# line5_2_2.net
KiCad netlist of a schematic drawn in EAGLE
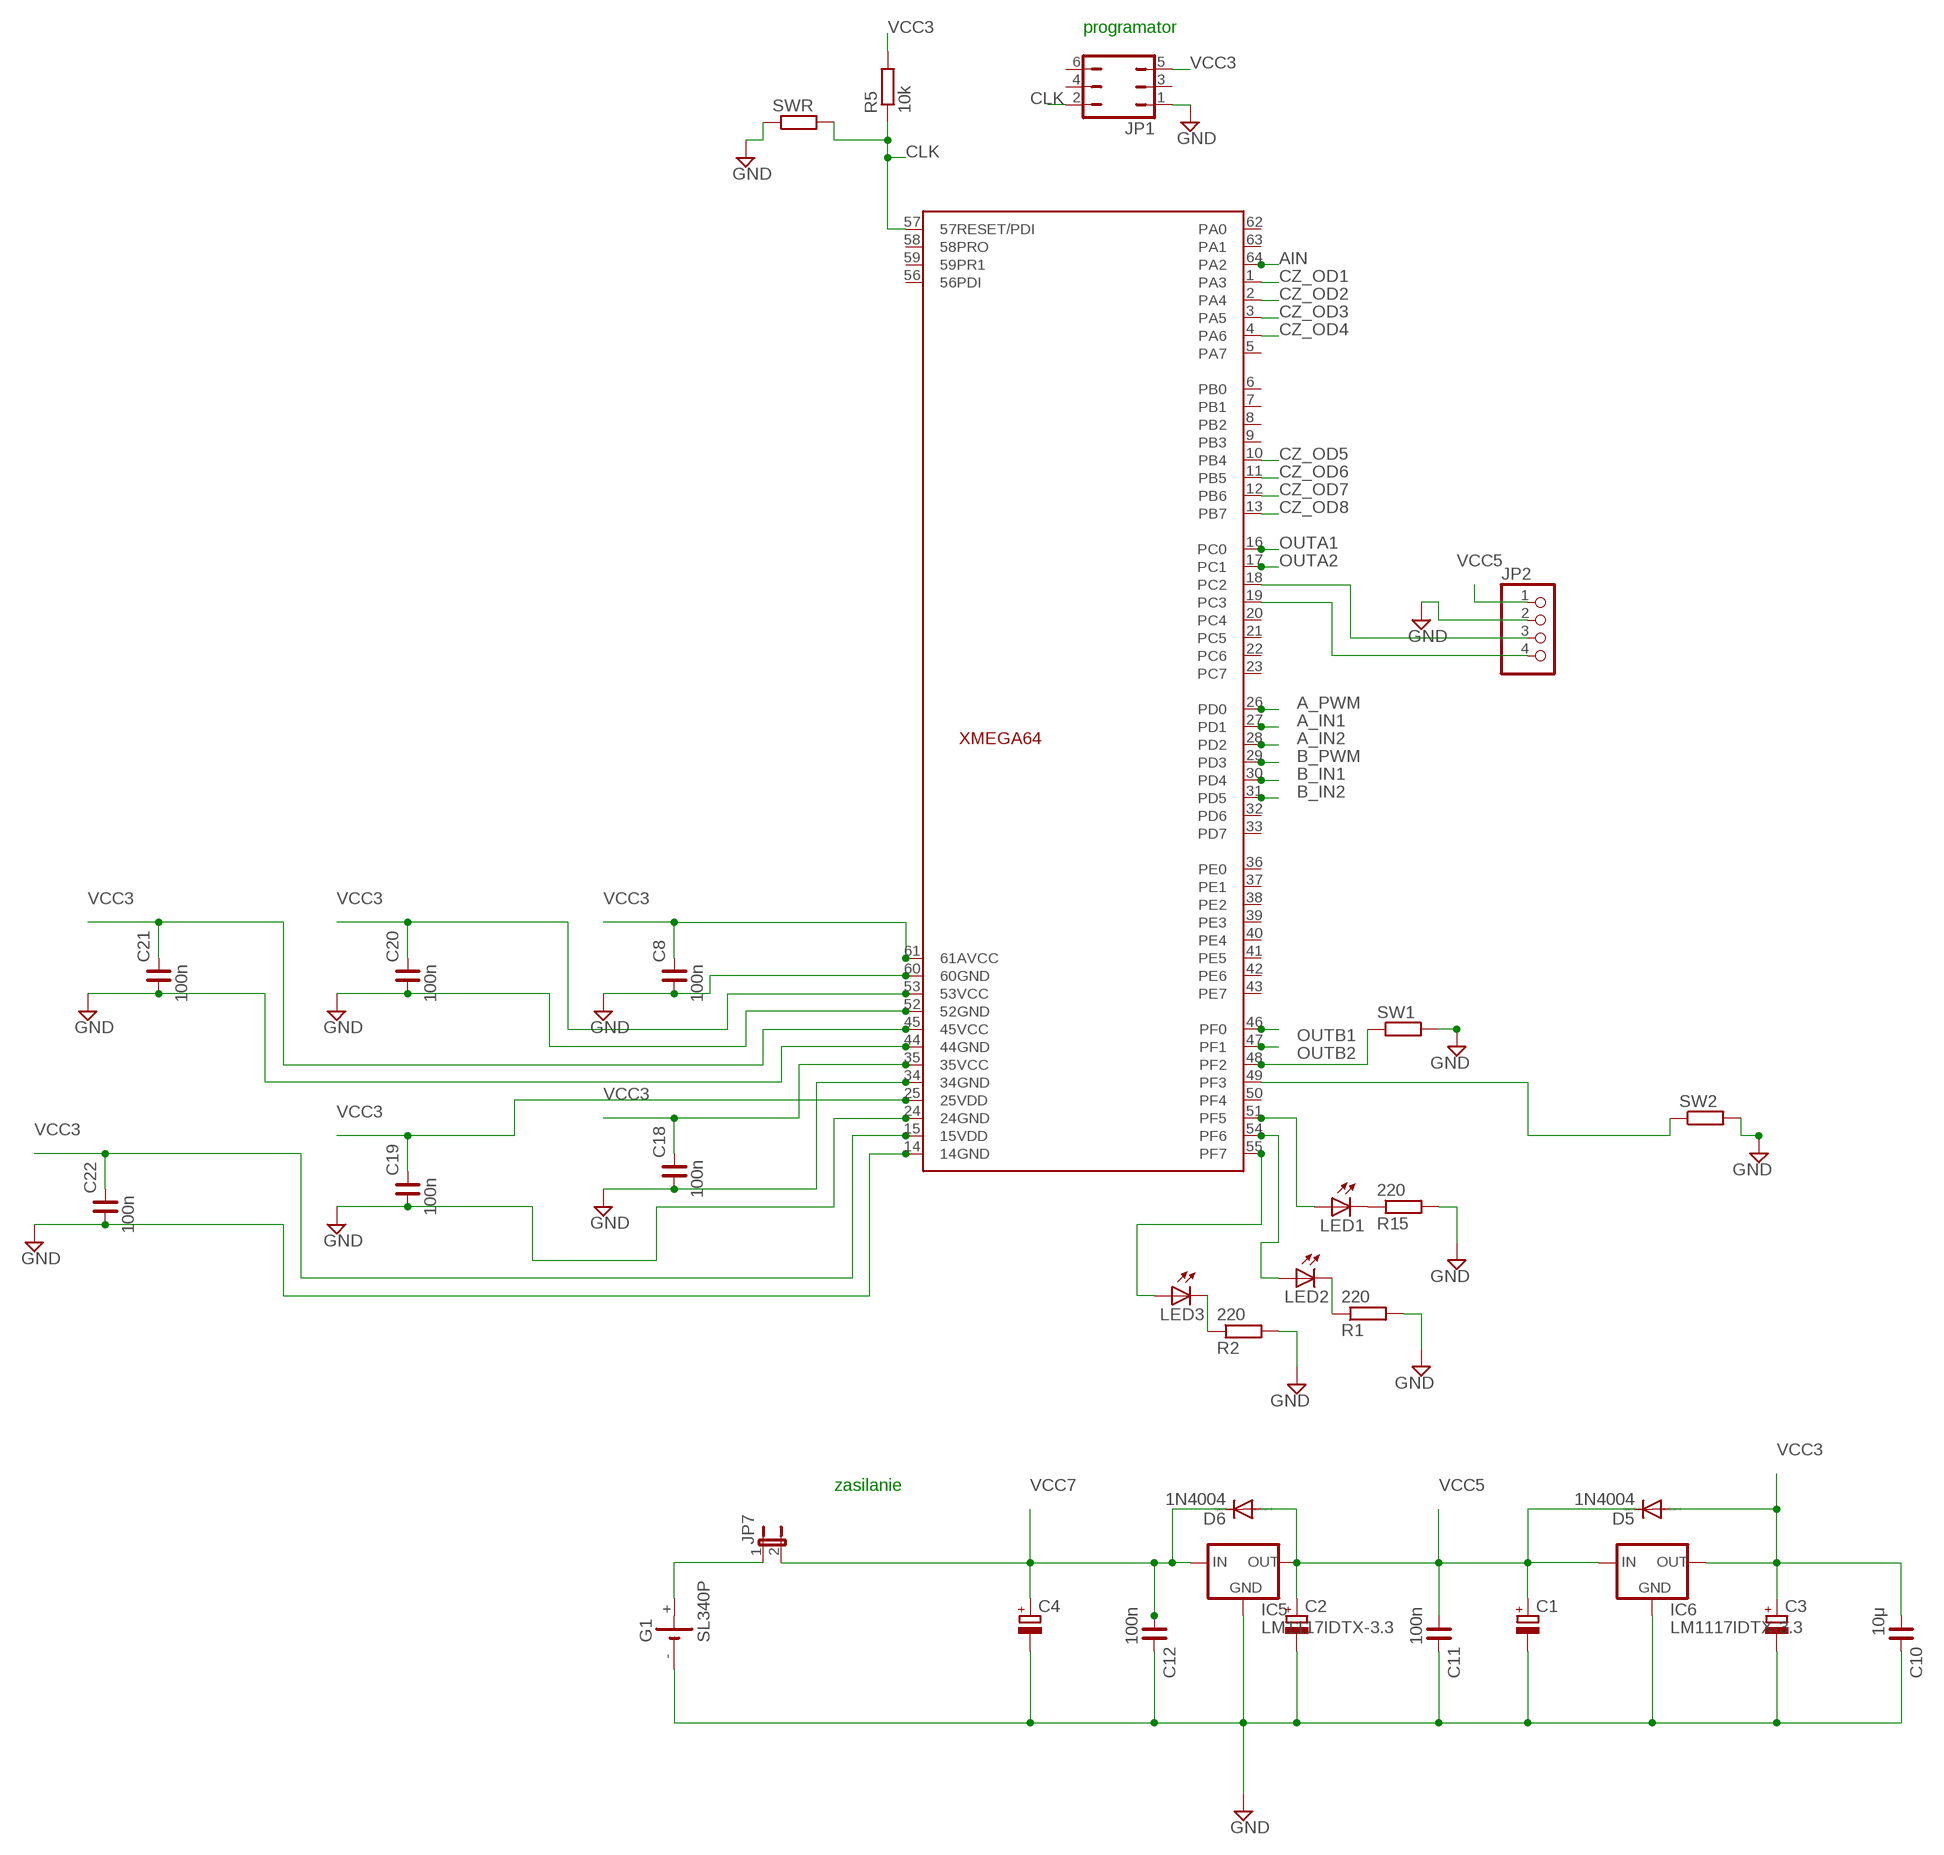
[diagram p0: schematic, sheet 1, part 1 of 2]
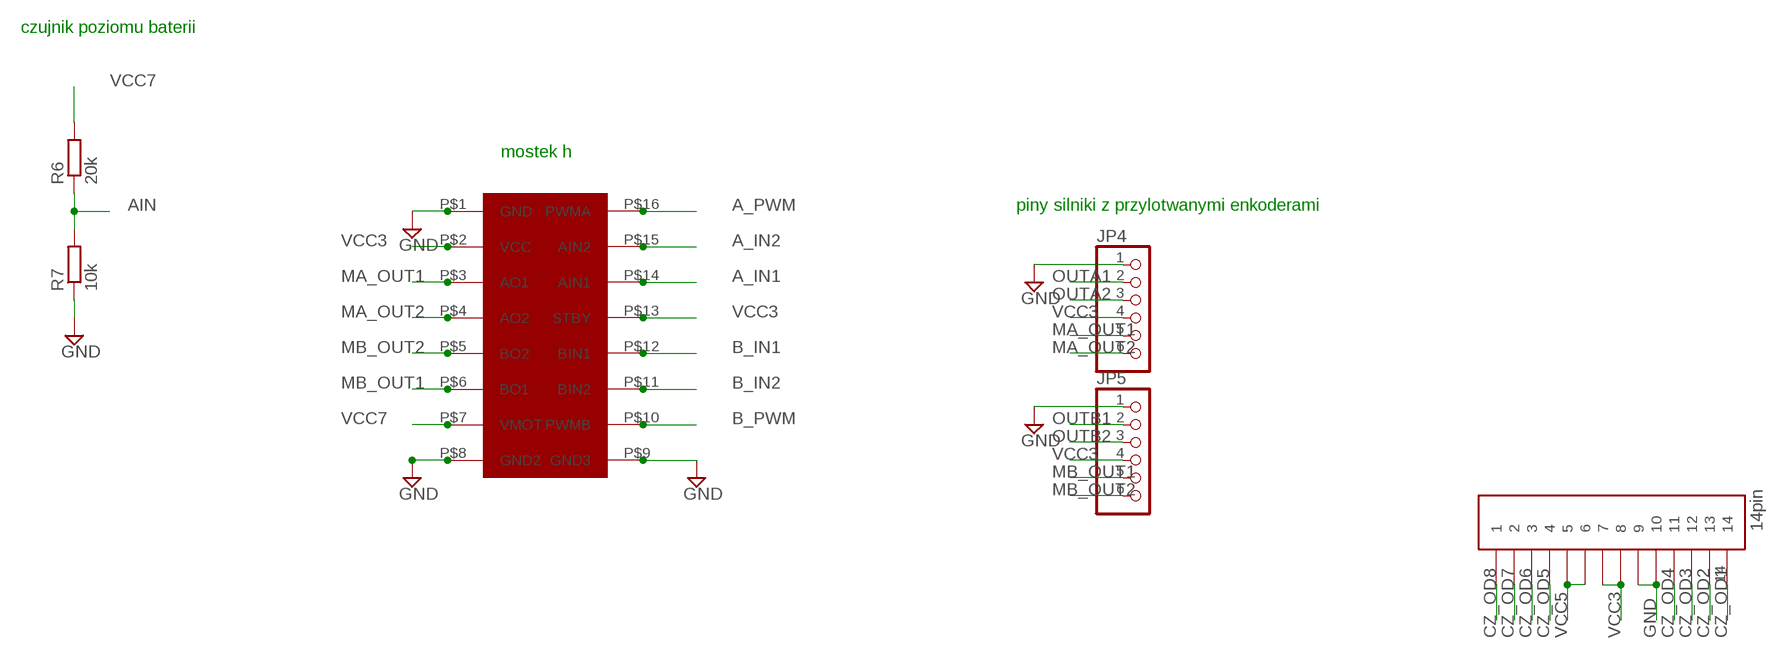
[diagram p1: schematic, sheet 1, part 2 of 2]

(export (version "E")
  (design (tool "Eeschema 10.0.6"))
  (components
    (comp (ref "C1")
      (value "CPOL-EU153CLV-0810")
      (footprint "eagle-import:153CLV-0810")
      (libsource (lib "eagle-import") (part "CPOL-EU153CLV-0810"))
    )
    (comp (ref "C2")
      (value "CPOL-EU153CLV-0810")
      (footprint "eagle-import:153CLV-0810")
      (libsource (lib "eagle-import") (part "CPOL-EU153CLV-0810"))
    )
    (comp (ref "C3")
      (value "CPOL-EU153CLV-0810")
      (footprint "eagle-import:153CLV-0810")
      (libsource (lib "eagle-import") (part "CPOL-EU153CLV-0810"))
    )
    (comp (ref "C4")
      (value "CPOL-EU153CLV-0810")
      (footprint "eagle-import:153CLV-0810")
      (libsource (lib "eagle-import") (part "CPOL-EU153CLV-0810"))
    )
    (comp (ref "C8")
      (value "100n")
      (footprint "eagle-import:C1206")
      (libsource (lib "eagle-import") (part "C_1206"))
    )
    (comp (ref "C10")
      (value "10μ")
      (footprint "eagle-import:C1206")
      (libsource (lib "eagle-import") (part "C_1206"))
    )
    (comp (ref "C11")
      (value "100n")
      (footprint "eagle-import:C1206")
      (libsource (lib "eagle-import") (part "C_1206"))
    )
    (comp (ref "C12")
      (value "100n")
      (footprint "eagle-import:C1206")
      (libsource (lib "eagle-import") (part "C_1206"))
    )
    (comp (ref "C18")
      (value "100n")
      (footprint "eagle-import:C1206")
      (libsource (lib "eagle-import") (part "C_1206"))
    )
    (comp (ref "C19")
      (value "100n")
      (footprint "eagle-import:C1206")
      (libsource (lib "eagle-import") (part "C_1206"))
    )
    (comp (ref "C20")
      (value "100n")
      (footprint "eagle-import:C1206")
      (libsource (lib "eagle-import") (part "C_1206"))
    )
    (comp (ref "C21")
      (value "100n")
      (footprint "eagle-import:C1206")
      (libsource (lib "eagle-import") (part "C_1206"))
    )
    (comp (ref "C22")
      (value "100n")
      (footprint "eagle-import:C1206")
      (libsource (lib "eagle-import") (part "C_1206"))
    )
    (comp (ref "D5")
      (value "1N4004")
      (footprint "eagle-import:DO41-10")
      (libsource (lib "eagle-import") (part "1N4004"))
    )
    (comp (ref "D6")
      (value "1N4004")
      (footprint "eagle-import:DO41-10")
      (libsource (lib "eagle-import") (part "1N4004"))
    )
    (comp (ref "G1")
      (value "SL340P")
      (footprint "eagle-import:SL-340_P3.6V")
      (libsource (lib "eagle-import") (part "SL340P"))
    )
    (comp (ref "IC5")
      (value "LM1117IDTX-3.3")
      (footprint "eagle-import:TO252")
      (libsource (lib "eagle-import") (part "LM1117IDTX-3.3"))
    )
    (comp (ref "IC6")
      (value "LM1117IDTX-3.3")
      (footprint "eagle-import:TO252")
      (libsource (lib "eagle-import") (part "LM1117IDTX-3.3"))
    )
    (comp (ref "JP1")
      (value "JP3Q")
      (footprint "eagle-import:JP3Q")
      (libsource (lib "eagle-import") (part "JP3Q"))
    )
    (comp (ref "JP2")
      (value "PINHD-1X4")
      (footprint "eagle-import:1X04")
      (libsource (lib "eagle-import") (part "PINHD-1X4"))
    )
    (comp (ref "JP4")
      (value "PINHD-1X6")
      (footprint "eagle-import:1X06")
      (libsource (lib "eagle-import") (part "PINHD-1X6"))
    )
    (comp (ref "JP5")
      (value "PINHD-1X6")
      (footprint "eagle-import:1X06")
      (libsource (lib "eagle-import") (part "PINHD-1X6"))
    )
    (comp (ref "JP7")
      (value "JP1E")
      (footprint "eagle-import:JP1")
      (libsource (lib "eagle-import") (part "JP1E"))
    )
    (comp (ref "LED1")
      (value "LEDSMT1206")
      (footprint "eagle-import:1206")
      (libsource (lib "eagle-import") (part "LEDSMT1206"))
    )
    (comp (ref "LED2")
      (value "LEDSMT1206")
      (footprint "eagle-import:1206")
      (libsource (lib "eagle-import") (part "LEDSMT1206"))
    )
    (comp (ref "LED3")
      (value "LEDSMT1206")
      (footprint "eagle-import:1206")
      (libsource (lib "eagle-import") (part "LEDSMT1206"))
    )
    (comp (ref "R1")
      (value "220")
      (footprint "eagle-import:R0805")
      (libsource (lib "eagle-import") (part "R-EU_R0805"))
    )
    (comp (ref "R2")
      (value "220")
      (footprint "eagle-import:R0805")
      (libsource (lib "eagle-import") (part "R-EU_R0805"))
    )
    (comp (ref "R5")
      (value "10k")
      (footprint "eagle-import:R0805")
      (libsource (lib "eagle-import") (part "R-EU_R0805"))
    )
    (comp (ref "R6")
      (value "20k")
      (footprint "eagle-import:R0805")
      (libsource (lib "eagle-import") (part "R-EU_R0805"))
    )
    (comp (ref "R7")
      (value "10k")
      (footprint "eagle-import:R0805")
      (libsource (lib "eagle-import") (part "R-EU_R0805"))
    )
    (comp (ref "R15")
      (value "220")
      (footprint "eagle-import:R0805")
      (libsource (lib "eagle-import") (part "R-EU_R0805"))
    )
    (comp (ref "SW1")
      (value "R-EU_R1206")
      (footprint "eagle-import:R1206")
      (libsource (lib "eagle-import") (part "R-EU_R1206"))
    )
    (comp (ref "SW2")
      (value "R-EU_R1206")
      (footprint "eagle-import:R1206")
      (libsource (lib "eagle-import") (part "R-EU_R1206"))
    )
    (comp (ref "SWR")
      (value "R-EU_R1206")
      (footprint "eagle-import:R1206")
      (libsource (lib "eagle-import") (part "R-EU_R1206"))
    )
    (comp (ref "U$1")
      (value "POLULU713")
      (footprint "eagle-import:POLULU713")
      (libsource (lib "eagle-import") (part "POLULU713"))
    )
    (comp (ref "U$2")
      (value "14PIN")
      (footprint "eagle-import:14PIN")
      (libsource (lib "eagle-import") (part "14PIN"))
    )
    (comp (ref "XMEGA64")
      (value "XMEGA64C3TQFP64")
      (footprint "eagle-import:TQFP64")
      (libsource (lib "eagle-import") (part "XMEGA64C3TQFP64"))
    )
  )
  (nets
    (net (code "1") (name "/AIN") (class "Default")
      (node (ref "R6") (pin "1") (pinfunction "1_1") (pintype "passive"))
      (node (ref "R7") (pin "2") (pinfunction "2_2") (pintype "passive"))
      (node (ref "XMEGA64") (pin "64") (pinfunction "PA2_64") (pintype "bidirectional"))
    )
    (net (code "2") (name "/A_IN1") (class "Default")
      (node (ref "U$1") (pin "P$14") (pinfunction "AIN1_P$14") (pintype "bidirectional"))
      (node (ref "XMEGA64") (pin "27") (pinfunction "PD1_27") (pintype "bidirectional"))
    )
    (net (code "3") (name "/A_IN2") (class "Default")
      (node (ref "U$1") (pin "P$15") (pinfunction "AIN2_P$15") (pintype "bidirectional"))
      (node (ref "XMEGA64") (pin "28") (pinfunction "PD2_28") (pintype "bidirectional"))
    )
    (net (code "4") (name "/A_PWM") (class "Default")
      (node (ref "U$1") (pin "P$16") (pinfunction "PWMA_P$16") (pintype "bidirectional"))
      (node (ref "XMEGA64") (pin "26") (pinfunction "PD0_26") (pintype "bidirectional"))
    )
    (net (code "5") (name "/B_IN1") (class "Default")
      (node (ref "U$1") (pin "P$12") (pinfunction "BIN1_P$12") (pintype "bidirectional"))
      (node (ref "XMEGA64") (pin "30") (pinfunction "PD4_30") (pintype "bidirectional"))
    )
    (net (code "6") (name "/B_IN2") (class "Default")
      (node (ref "U$1") (pin "P$11") (pinfunction "BIN2_P$11") (pintype "bidirectional"))
      (node (ref "XMEGA64") (pin "31") (pinfunction "PD5_31") (pintype "bidirectional"))
    )
    (net (code "7") (name "/B_PWM") (class "Default")
      (node (ref "U$1") (pin "P$10") (pinfunction "PWMB_P$10") (pintype "bidirectional"))
      (node (ref "XMEGA64") (pin "29") (pinfunction "PD3_29") (pintype "bidirectional"))
    )
    (net (code "8") (name "/CLK") (class "Default")
      (node (ref "JP1") (pin "2") (pinfunction "2_2") (pintype "passive"))
      (node (ref "R5") (pin "1") (pinfunction "1_1") (pintype "passive"))
      (node (ref "SWR") (pin "2") (pinfunction "2_2") (pintype "passive"))
      (node (ref "XMEGA64") (pin "57") (pinfunction "57RESET/PDI_57") (pintype "bidirectional"))
    )
    (net (code "9") (name "/CZ_OD1") (class "Default")
      (node (ref "U$2") (pin "14") (pinfunction "14_14") (pintype "bidirectional"))
      (node (ref "XMEGA64") (pin "1") (pinfunction "PA3_1") (pintype "bidirectional"))
    )
    (net (code "10") (name "/CZ_OD2") (class "Default")
      (node (ref "U$2") (pin "13") (pinfunction "13_13") (pintype "bidirectional"))
      (node (ref "XMEGA64") (pin "2") (pinfunction "PA4_2") (pintype "bidirectional"))
    )
    (net (code "11") (name "/CZ_OD3") (class "Default")
      (node (ref "U$2") (pin "12") (pinfunction "12_12") (pintype "bidirectional"))
      (node (ref "XMEGA64") (pin "3") (pinfunction "PA5_3") (pintype "bidirectional"))
    )
    (net (code "12") (name "/CZ_OD4") (class "Default")
      (node (ref "U$2") (pin "11") (pinfunction "11_11") (pintype "bidirectional"))
      (node (ref "XMEGA64") (pin "4") (pinfunction "PA6_4") (pintype "bidirectional"))
    )
    (net (code "13") (name "/CZ_OD5") (class "Default")
      (node (ref "U$2") (pin "4") (pinfunction "4_4") (pintype "bidirectional"))
      (node (ref "XMEGA64") (pin "10") (pinfunction "PB4_10") (pintype "bidirectional"))
    )
    (net (code "14") (name "/CZ_OD6") (class "Default")
      (node (ref "U$2") (pin "3") (pinfunction "3_3") (pintype "bidirectional"))
      (node (ref "XMEGA64") (pin "11") (pinfunction "PB5_11") (pintype "bidirectional"))
    )
    (net (code "15") (name "/CZ_OD7") (class "Default")
      (node (ref "U$2") (pin "2") (pinfunction "2_2") (pintype "bidirectional"))
      (node (ref "XMEGA64") (pin "12") (pinfunction "PB6_12") (pintype "bidirectional"))
    )
    (net (code "16") (name "/CZ_OD8") (class "Default")
      (node (ref "U$2") (pin "1") (pinfunction "1_1") (pintype "bidirectional"))
      (node (ref "XMEGA64") (pin "13") (pinfunction "PB7_13") (pintype "bidirectional"))
    )
    (net (code "17") (name "/MA_OUT1") (class "Default")
      (node (ref "JP4") (pin "5") (pinfunction "5_5") (pintype "passive"))
      (node (ref "U$1") (pin "P$3") (pinfunction "AO1_P$3") (pintype "bidirectional"))
    )
    (net (code "18") (name "/MA_OUT2") (class "Default")
      (node (ref "JP4") (pin "6") (pinfunction "6_6") (pintype "passive"))
      (node (ref "U$1") (pin "P$4") (pinfunction "AO2_P$4") (pintype "bidirectional"))
    )
    (net (code "19") (name "/MB_OUT1") (class "Default")
      (node (ref "JP5") (pin "5") (pinfunction "5_5") (pintype "passive"))
      (node (ref "U$1") (pin "P$6") (pinfunction "BO1_P$6") (pintype "bidirectional"))
    )
    (net (code "20") (name "/MB_OUT2") (class "Default")
      (node (ref "JP5") (pin "6") (pinfunction "6_6") (pintype "passive"))
      (node (ref "U$1") (pin "P$5") (pinfunction "BO2_P$5") (pintype "bidirectional"))
    )
    (net (code "21") (name "/OUTA1") (class "Default")
      (node (ref "JP4") (pin "2") (pinfunction "2_2") (pintype "passive"))
      (node (ref "XMEGA64") (pin "16") (pinfunction "PC0_16") (pintype "bidirectional"))
    )
    (net (code "22") (name "/OUTA2") (class "Default")
      (node (ref "JP4") (pin "3") (pinfunction "3_3") (pintype "passive"))
      (node (ref "XMEGA64") (pin "17") (pinfunction "PC1_17") (pintype "bidirectional"))
    )
    (net (code "23") (name "/OUTB1") (class "Default")
      (node (ref "JP5") (pin "2") (pinfunction "2_2") (pintype "passive"))
      (node (ref "XMEGA64") (pin "46") (pinfunction "PF0_46") (pintype "bidirectional"))
    )
    (net (code "24") (name "/OUTB2") (class "Default")
      (node (ref "JP5") (pin "3") (pinfunction "3_3") (pintype "passive"))
      (node (ref "XMEGA64") (pin "47") (pinfunction "PF1_47") (pintype "bidirectional"))
    )
    (net (code "25") (name "/VCC3") (class "Default")
      (node (ref "C10") (pin "1") (pinfunction "1_1") (pintype "passive"))
      (node (ref "C18") (pin "2") (pinfunction "2_2") (pintype "passive"))
      (node (ref "C19") (pin "2") (pinfunction "2_2") (pintype "passive"))
      (node (ref "C20") (pin "2") (pinfunction "2_2") (pintype "passive"))
      (node (ref "C21") (pin "2") (pinfunction "2_2") (pintype "passive"))
      (node (ref "C22") (pin "2") (pinfunction "2_2") (pintype "passive"))
      (node (ref "C3") (pin "+") (pinfunction "+_+") (pintype "passive"))
      (node (ref "C8") (pin "2") (pinfunction "2_2") (pintype "passive"))
      (node (ref "D5") (pin "A") (pinfunction "A_A") (pintype "passive"))
      (node (ref "IC6") (pin "TAB") (pinfunction "OUT_TAB") (pintype "passive"))
      (node (ref "JP1") (pin "5") (pinfunction "5_5") (pintype "passive"))
      (node (ref "JP4") (pin "4") (pinfunction "4_4") (pintype "passive"))
      (node (ref "JP5") (pin "4") (pinfunction "4_4") (pintype "passive"))
      (node (ref "R5") (pin "2") (pinfunction "2_2") (pintype "passive"))
      (node (ref "U$1") (pin "P$13") (pinfunction "STBY_P$13") (pintype "bidirectional"))
      (node (ref "U$1") (pin "P$2") (pinfunction "VCC_P$2") (pintype "bidirectional"))
      (node (ref "U$2") (pin "7") (pinfunction "7_7") (pintype "bidirectional"))
      (node (ref "U$2") (pin "8") (pinfunction "8_8") (pintype "bidirectional"))
      (node (ref "XMEGA64") (pin "15") (pinfunction "15VDD_15") (pintype "power_in"))
      (node (ref "XMEGA64") (pin "25") (pinfunction "25VDD_25") (pintype "power_in"))
      (node (ref "XMEGA64") (pin "35") (pinfunction "35VCC_35") (pintype "power_in"))
      (node (ref "XMEGA64") (pin "45") (pinfunction "45VCC_45") (pintype "power_in"))
      (node (ref "XMEGA64") (pin "53") (pinfunction "53VCC_53") (pintype "power_in"))
      (node (ref "XMEGA64") (pin "61") (pinfunction "61AVCC_61") (pintype "power_in"))
    )
    (net (code "26") (name "/VCC5") (class "Default")
      (node (ref "C1") (pin "+") (pinfunction "+_+") (pintype "passive"))
      (node (ref "C11") (pin "1") (pinfunction "1_1") (pintype "passive"))
      (node (ref "C2") (pin "+") (pinfunction "+_+") (pintype "passive"))
      (node (ref "D5") (pin "C") (pinfunction "C_C") (pintype "passive"))
      (node (ref "D6") (pin "A") (pinfunction "A_A") (pintype "passive"))
      (node (ref "IC5") (pin "TAB") (pinfunction "OUT_TAB") (pintype "passive"))
      (node (ref "IC6") (pin "2") (pinfunction "IN_2") (pintype "input"))
      (node (ref "JP2") (pin "1") (pinfunction "1_1") (pintype "passive"))
      (node (ref "U$2") (pin "5") (pinfunction "5_5") (pintype "bidirectional"))
      (node (ref "U$2") (pin "6") (pinfunction "6_6") (pintype "bidirectional"))
    )
    (net (code "27") (name "/VCC7") (class "Default")
      (node (ref "C12") (pin "1") (pinfunction "1_1") (pintype "passive"))
      (node (ref "C4") (pin "+") (pinfunction "+_+") (pintype "passive"))
      (node (ref "D6") (pin "C") (pinfunction "C_C") (pintype "passive"))
      (node (ref "IC5") (pin "2") (pinfunction "IN_2") (pintype "input"))
      (node (ref "JP7") (pin "2") (pinfunction "2_2") (pintype "passive"))
      (node (ref "R6") (pin "2") (pinfunction "2_2") (pintype "passive"))
      (node (ref "U$1") (pin "P$7") (pinfunction "VMOT_P$7") (pintype "bidirectional"))
    )
    (net (code "28") (name "GND") (class "Default")
      (node (ref "C1") (pin "-") (pinfunction "-_-") (pintype "passive"))
      (node (ref "C10") (pin "2") (pinfunction "2_2") (pintype "passive"))
      (node (ref "C11") (pin "2") (pinfunction "2_2") (pintype "passive"))
      (node (ref "C12") (pin "2") (pinfunction "2_2") (pintype "passive"))
      (node (ref "C18") (pin "1") (pinfunction "1_1") (pintype "passive"))
      (node (ref "C19") (pin "1") (pinfunction "1_1") (pintype "passive"))
      (node (ref "C2") (pin "-") (pinfunction "-_-") (pintype "passive"))
      (node (ref "C20") (pin "1") (pinfunction "1_1") (pintype "passive"))
      (node (ref "C21") (pin "1") (pinfunction "1_1") (pintype "passive"))
      (node (ref "C22") (pin "1") (pinfunction "1_1") (pintype "passive"))
      (node (ref "C3") (pin "-") (pinfunction "-_-") (pintype "passive"))
      (node (ref "C4") (pin "-") (pinfunction "-_-") (pintype "passive"))
      (node (ref "C8") (pin "1") (pinfunction "1_1") (pintype "passive"))
      (node (ref "G1") (pin "-") (pinfunction "-_-") (pintype "passive"))
      (node (ref "IC5") (pin "1") (pinfunction "GND_1") (pintype "input"))
      (node (ref "IC6") (pin "1") (pinfunction "GND_1") (pintype "input"))
      (node (ref "JP1") (pin "1") (pinfunction "1_1") (pintype "passive"))
      (node (ref "JP2") (pin "2") (pinfunction "2_2") (pintype "passive"))
      (node (ref "JP4") (pin "1") (pinfunction "1_1") (pintype "passive"))
      (node (ref "JP5") (pin "1") (pinfunction "1_1") (pintype "passive"))
      (node (ref "R1") (pin "2") (pinfunction "2_2") (pintype "passive"))
      (node (ref "R15") (pin "2") (pinfunction "2_2") (pintype "passive"))
      (node (ref "R2") (pin "2") (pinfunction "2_2") (pintype "passive"))
      (node (ref "R7") (pin "1") (pinfunction "1_1") (pintype "passive"))
      (node (ref "SW1") (pin "2") (pinfunction "2_2") (pintype "passive"))
      (node (ref "SW2") (pin "2") (pinfunction "2_2") (pintype "passive"))
      (node (ref "SWR") (pin "1") (pinfunction "1_1") (pintype "passive"))
      (node (ref "U$1") (pin "P$1") (pinfunction "GND_P$1") (pintype "bidirectional"))
      (node (ref "U$1") (pin "P$8") (pinfunction "GND2_P$8") (pintype "bidirectional"))
      (node (ref "U$1") (pin "P$9") (pinfunction "GND3_P$9") (pintype "bidirectional"))
      (node (ref "U$2") (pin "10") (pinfunction "10_10") (pintype "bidirectional"))
      (node (ref "U$2") (pin "9") (pinfunction "9_9") (pintype "bidirectional"))
      (node (ref "XMEGA64") (pin "14") (pinfunction "14GND_14") (pintype "power_in"))
      (node (ref "XMEGA64") (pin "24") (pinfunction "24GND_24") (pintype "power_in"))
      (node (ref "XMEGA64") (pin "34") (pinfunction "34GND_34") (pintype "power_in"))
      (node (ref "XMEGA64") (pin "44") (pinfunction "44GND_44") (pintype "power_in"))
      (node (ref "XMEGA64") (pin "52") (pinfunction "52GND_52") (pintype "power_in"))
      (node (ref "XMEGA64") (pin "60") (pinfunction "60GND_60") (pintype "power_in"))
    )
    (net (code "29") (name "Net-(G1-Pad+)") (class "Default")
      (node (ref "G1") (pin "+") (pinfunction "+_+") (pintype "passive"))
      (node (ref "JP7") (pin "1") (pinfunction "1_1") (pintype "passive"))
    )
    (net (code "30") (name "Net-(LED1-PadC)") (class "Default")
      (node (ref "LED1") (pin "C") (pinfunction "C_C") (pintype "passive"))
      (node (ref "R15") (pin "1") (pinfunction "1_1") (pintype "passive"))
    )
    (net (code "31") (name "Net-(LED2-PadC)") (class "Default")
      (node (ref "LED2") (pin "C") (pinfunction "C_C") (pintype "passive"))
      (node (ref "R1") (pin "1") (pinfunction "1_1") (pintype "passive"))
    )
    (net (code "32") (name "Net-(LED3-PadC)") (class "Default")
      (node (ref "LED3") (pin "C") (pinfunction "C_C") (pintype "passive"))
      (node (ref "R2") (pin "1") (pinfunction "1_1") (pintype "passive"))
    )
    (net (code "33") (name "Net-(XMEGA64-PC2)") (class "Default")
      (node (ref "JP2") (pin "3") (pinfunction "3_3") (pintype "passive"))
      (node (ref "XMEGA64") (pin "18") (pinfunction "PC2_18") (pintype "bidirectional"))
    )
    (net (code "34") (name "Net-(XMEGA64-PC3)") (class "Default")
      (node (ref "JP2") (pin "4") (pinfunction "4_4") (pintype "passive"))
      (node (ref "XMEGA64") (pin "19") (pinfunction "PC3_19") (pintype "bidirectional"))
    )
    (net (code "35") (name "Net-(XMEGA64-PF2)") (class "Default")
      (node (ref "SW1") (pin "1") (pinfunction "1_1") (pintype "passive"))
      (node (ref "XMEGA64") (pin "48") (pinfunction "PF2_48") (pintype "bidirectional"))
    )
    (net (code "36") (name "Net-(XMEGA64-PF3)") (class "Default")
      (node (ref "SW2") (pin "1") (pinfunction "1_1") (pintype "passive"))
      (node (ref "XMEGA64") (pin "49") (pinfunction "PF3_49") (pintype "bidirectional"))
    )
    (net (code "37") (name "Net-(XMEGA64-PF5)") (class "Default")
      (node (ref "LED1") (pin "A") (pinfunction "A_A") (pintype "passive"))
      (node (ref "XMEGA64") (pin "51") (pinfunction "PF5_51") (pintype "bidirectional"))
    )
    (net (code "38") (name "Net-(XMEGA64-PF6)") (class "Default")
      (node (ref "LED2") (pin "A") (pinfunction "A_A") (pintype "passive"))
      (node (ref "XMEGA64") (pin "54") (pinfunction "PF6_54") (pintype "bidirectional"))
    )
    (net (code "39") (name "Net-(XMEGA64-PF7)") (class "Default")
      (node (ref "LED3") (pin "A") (pinfunction "A_A") (pintype "passive"))
      (node (ref "XMEGA64") (pin "55") (pinfunction "PF7_55") (pintype "bidirectional"))
    )
    (net (code "40") (name "unconnected-(JP1-Pad3)") (class "Default")
      (node (ref "JP1") (pin "3") (pinfunction "3_3") (pintype "passive"))
    )
    (net (code "41") (name "unconnected-(JP1-Pad4)") (class "Default")
      (node (ref "JP1") (pin "4") (pinfunction "4_4") (pintype "passive"))
    )
    (net (code "42") (name "unconnected-(JP1-Pad6)") (class "Default")
      (node (ref "JP1") (pin "6") (pinfunction "6_6") (pintype "passive"))
    )
    (net (code "43") (name "unconnected-(XMEGA64-56PDI-Pad56)") (class "Default")
      (node (ref "XMEGA64") (pin "56") (pinfunction "56PDI_56") (pintype "bidirectional"))
    )
    (net (code "44") (name "unconnected-(XMEGA64-58PRO-Pad58)") (class "Default")
      (node (ref "XMEGA64") (pin "58") (pinfunction "58PRO_58") (pintype "bidirectional"))
    )
    (net (code "45") (name "unconnected-(XMEGA64-59PR1-Pad59)") (class "Default")
      (node (ref "XMEGA64") (pin "59") (pinfunction "59PR1_59") (pintype "bidirectional"))
    )
    (net (code "46") (name "unconnected-(XMEGA64-PA0-Pad62)") (class "Default")
      (node (ref "XMEGA64") (pin "62") (pinfunction "PA0_62") (pintype "bidirectional"))
    )
    (net (code "47") (name "unconnected-(XMEGA64-PA1-Pad63)") (class "Default")
      (node (ref "XMEGA64") (pin "63") (pinfunction "PA1_63") (pintype "bidirectional"))
    )
    (net (code "48") (name "unconnected-(XMEGA64-PA7-Pad5)") (class "Default")
      (node (ref "XMEGA64") (pin "5") (pinfunction "PA7_5") (pintype "bidirectional"))
    )
    (net (code "49") (name "unconnected-(XMEGA64-PB0-Pad6)") (class "Default")
      (node (ref "XMEGA64") (pin "6") (pinfunction "PB0_6") (pintype "bidirectional"))
    )
    (net (code "50") (name "unconnected-(XMEGA64-PB1-Pad7)") (class "Default")
      (node (ref "XMEGA64") (pin "7") (pinfunction "PB1_7") (pintype "bidirectional"))
    )
    (net (code "51") (name "unconnected-(XMEGA64-PB2-Pad8)") (class "Default")
      (node (ref "XMEGA64") (pin "8") (pinfunction "PB2_8") (pintype "bidirectional"))
    )
    (net (code "52") (name "unconnected-(XMEGA64-PB3-Pad9)") (class "Default")
      (node (ref "XMEGA64") (pin "9") (pinfunction "PB3_9") (pintype "bidirectional"))
    )
    (net (code "53") (name "unconnected-(XMEGA64-PC4-Pad20)") (class "Default")
      (node (ref "XMEGA64") (pin "20") (pinfunction "PC4_20") (pintype "bidirectional"))
    )
    (net (code "54") (name "unconnected-(XMEGA64-PC5-Pad21)") (class "Default")
      (node (ref "XMEGA64") (pin "21") (pinfunction "PC5_21") (pintype "bidirectional"))
    )
    (net (code "55") (name "unconnected-(XMEGA64-PC6-Pad22)") (class "Default")
      (node (ref "XMEGA64") (pin "22") (pinfunction "PC6_22") (pintype "bidirectional"))
    )
    (net (code "56") (name "unconnected-(XMEGA64-PC7-Pad23)") (class "Default")
      (node (ref "XMEGA64") (pin "23") (pinfunction "PC7_23") (pintype "bidirectional"))
    )
    (net (code "57") (name "unconnected-(XMEGA64-PD6-Pad32)") (class "Default")
      (node (ref "XMEGA64") (pin "32") (pinfunction "PD6_32") (pintype "bidirectional"))
    )
    (net (code "58") (name "unconnected-(XMEGA64-PD7-Pad33)") (class "Default")
      (node (ref "XMEGA64") (pin "33") (pinfunction "PD7_33") (pintype "bidirectional"))
    )
    (net (code "59") (name "unconnected-(XMEGA64-PE0-Pad36)") (class "Default")
      (node (ref "XMEGA64") (pin "36") (pinfunction "PE0_36") (pintype "bidirectional"))
    )
    (net (code "60") (name "unconnected-(XMEGA64-PE1-Pad37)") (class "Default")
      (node (ref "XMEGA64") (pin "37") (pinfunction "PE1_37") (pintype "bidirectional"))
    )
    (net (code "61") (name "unconnected-(XMEGA64-PE2-Pad38)") (class "Default")
      (node (ref "XMEGA64") (pin "38") (pinfunction "PE2_38") (pintype "bidirectional"))
    )
    (net (code "62") (name "unconnected-(XMEGA64-PE3-Pad39)") (class "Default")
      (node (ref "XMEGA64") (pin "39") (pinfunction "PE3_39") (pintype "bidirectional"))
    )
    (net (code "63") (name "unconnected-(XMEGA64-PE4-Pad40)") (class "Default")
      (node (ref "XMEGA64") (pin "40") (pinfunction "PE4_40") (pintype "bidirectional"))
    )
    (net (code "64") (name "unconnected-(XMEGA64-PE5-Pad41)") (class "Default")
      (node (ref "XMEGA64") (pin "41") (pinfunction "PE5_41") (pintype "bidirectional"))
    )
    (net (code "65") (name "unconnected-(XMEGA64-PE6-Pad42)") (class "Default")
      (node (ref "XMEGA64") (pin "42") (pinfunction "PE6_42") (pintype "bidirectional"))
    )
    (net (code "66") (name "unconnected-(XMEGA64-PE7-Pad43)") (class "Default")
      (node (ref "XMEGA64") (pin "43") (pinfunction "PE7_43") (pintype "bidirectional"))
    )
    (net (code "67") (name "unconnected-(XMEGA64-PF4-Pad50)") (class "Default")
      (node (ref "XMEGA64") (pin "50") (pinfunction "PF4_50") (pintype "bidirectional"))
    )
  )
)
